# ProDoc_Schematic1_2026-04-23.net
KiCad netlist of a schematic drawn in EasyEDA Pro
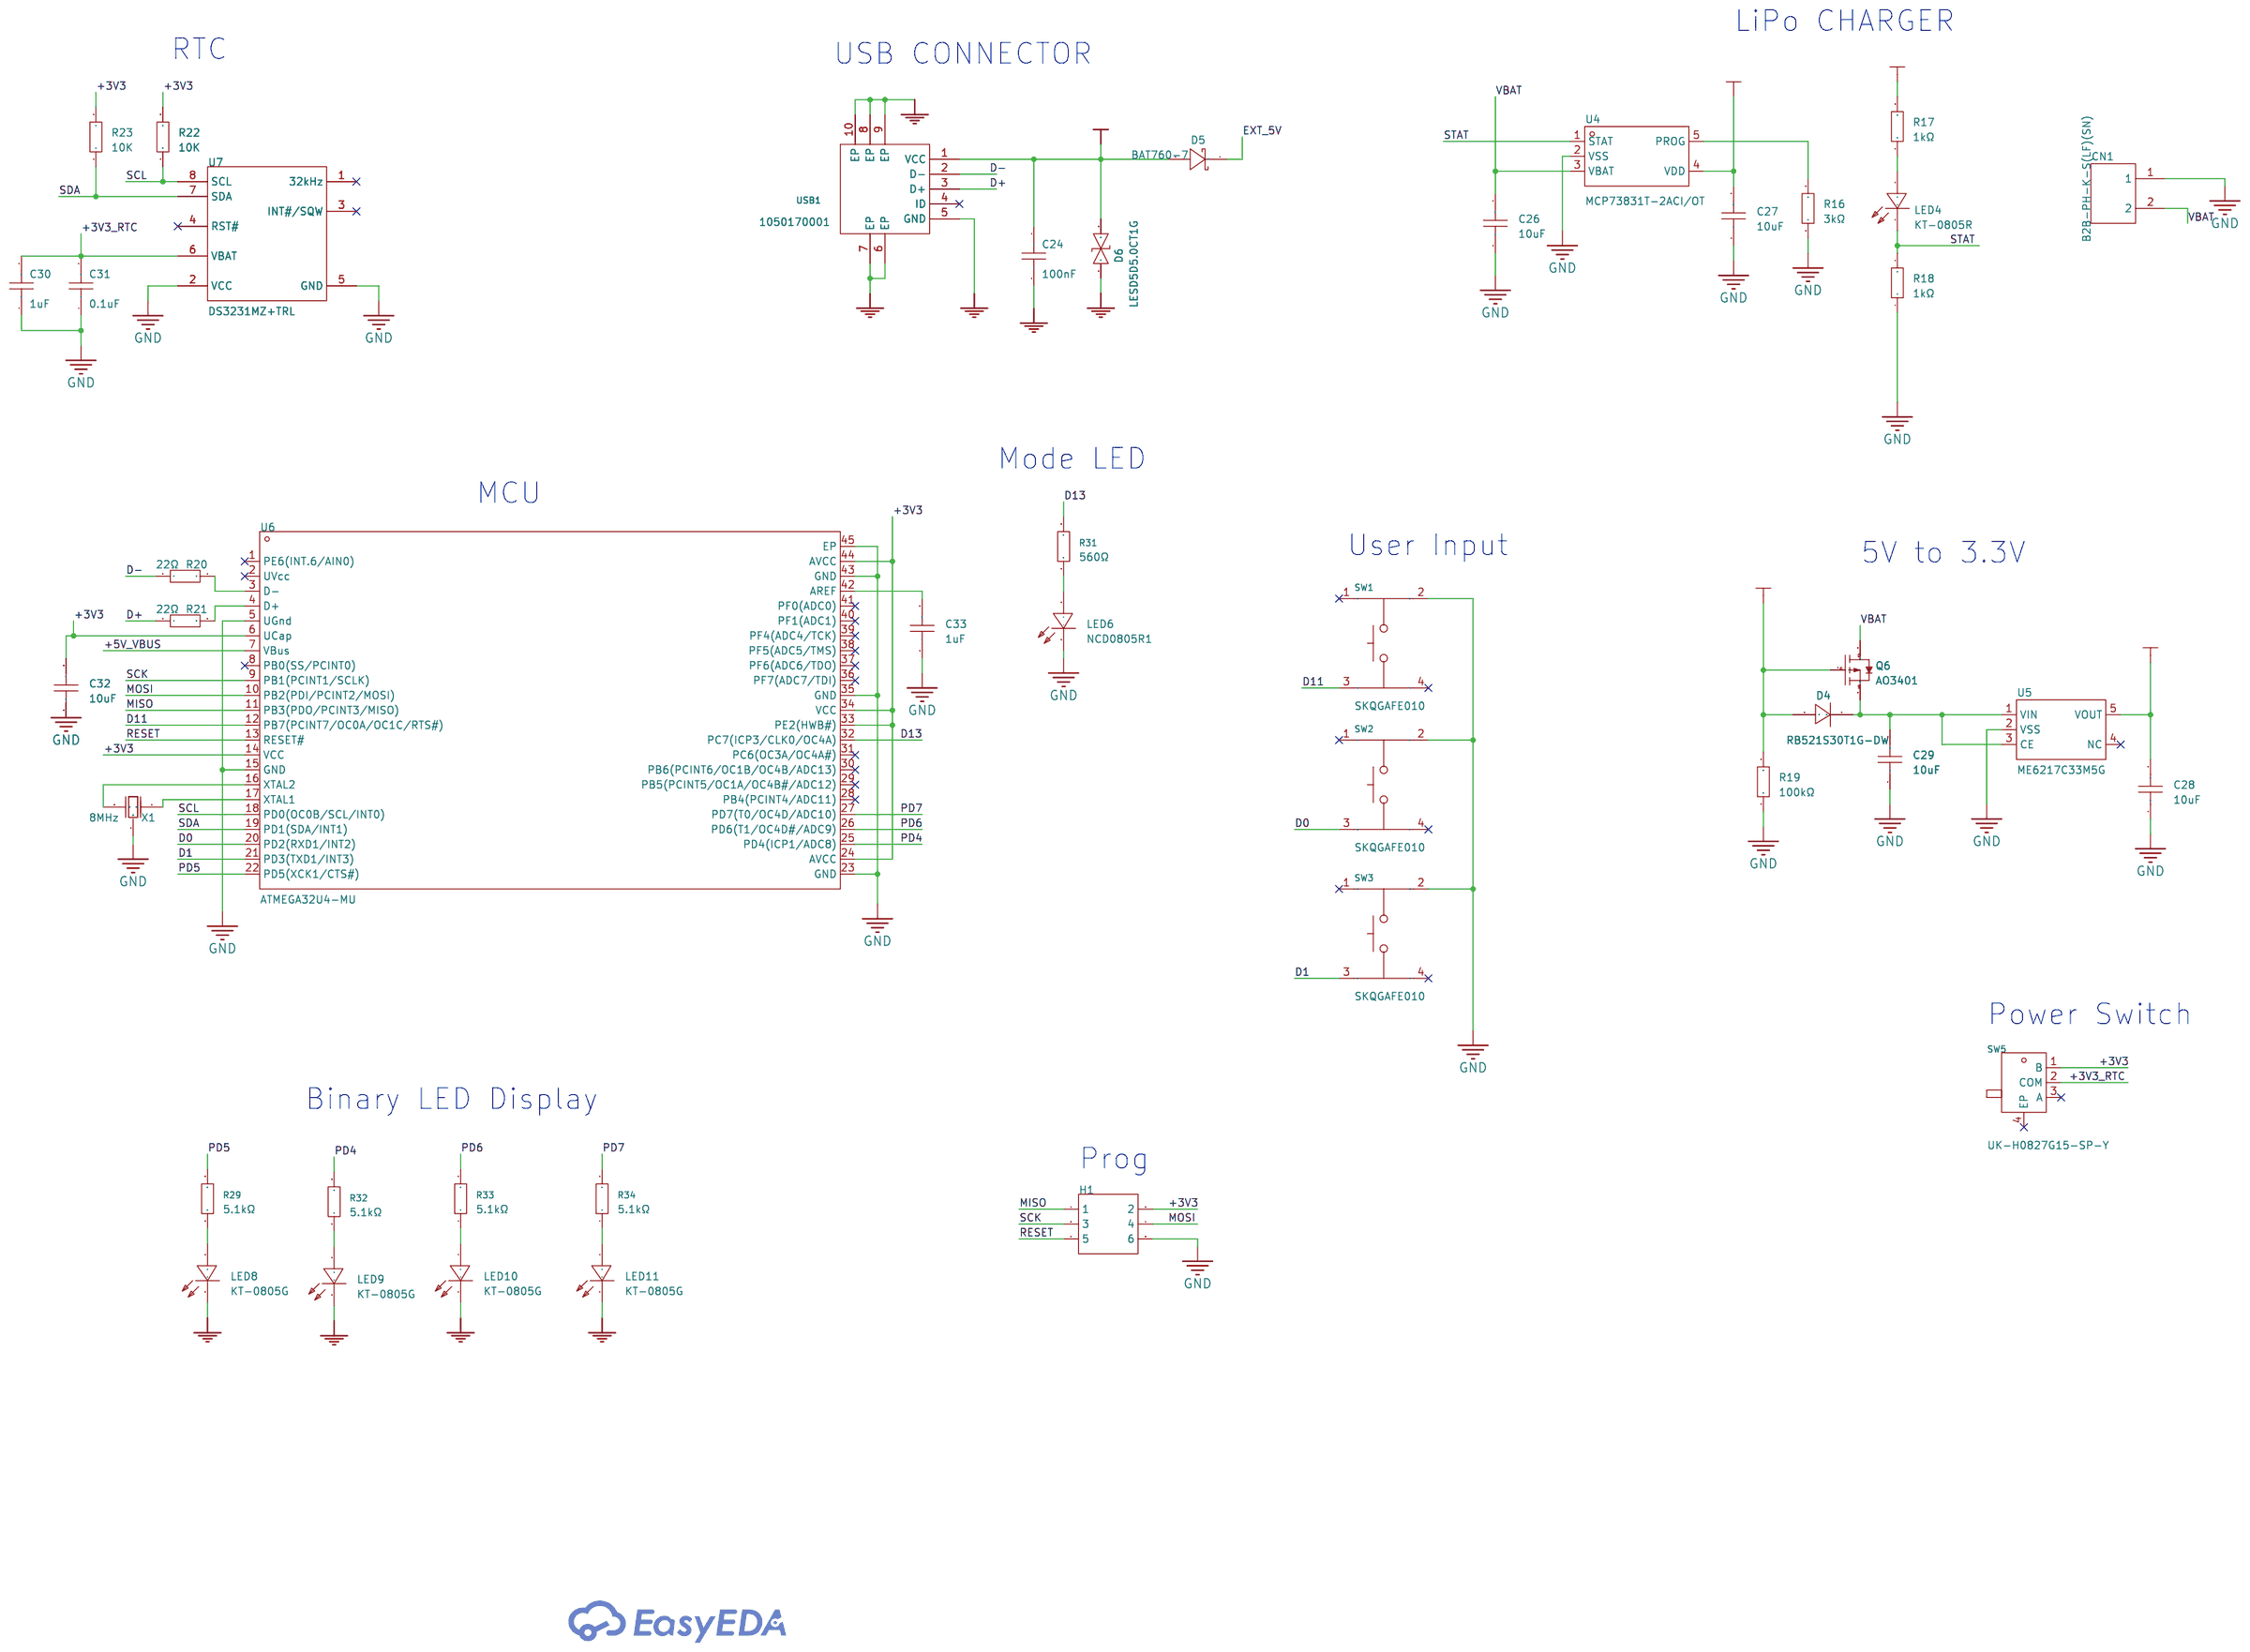
[diagram p0: schematic sheet]

(export (version "E")
  (design (tool "Eeschema 10.0.6"))
  (components
    (comp (ref "C24")
      (value "100nF")
      (footprint "easyedapro:C0402")
      (description "Capacitance:100nF Tolerance:±10% Tolerance:±10% Voltage Rating:16V Temperature Coefficient:X7R")
      (fields
        (field (name "Manufacturer Part") "CL05B104KO5NNNC")
        (field (name "Manufacturer") "SAMSUNG(三星)")
      )
      (libsource (lib "easyedapro") (part "CL05B104KO5NNNC"))
    )
    (comp (ref "C26")
      (value "10uF")
      (footprint "easyedapro:C0402")
      (description "Capacitance:10uF Tolerance:±20% Tolerance:±20% Voltage Rating:10V Temperature Coefficient:X5R")
      (fields
        (field (name "Manufacturer Part") "CL05A106MP5NUNC")
        (field (name "Manufacturer") "SAMSUNG(三星)")
      )
      (libsource (lib "easyedapro") (part "CL05A106MP5NUNC_C315248"))
    )
    (comp (ref "C27")
      (value "10uF")
      (footprint "easyedapro:C0402")
      (description "Capacitance:10uF Tolerance:±20% Tolerance:±20% Voltage Rating:10V Temperature Coefficient:X5R")
      (fields
        (field (name "Manufacturer Part") "CL05A106MP5NUNC")
        (field (name "Manufacturer") "SAMSUNG(三星)")
      )
      (libsource (lib "easyedapro") (part "CL05A106MP5NUNC_C315248"))
    )
    (comp (ref "C28")
      (value "10uF")
      (footprint "easyedapro:C0402")
      (description "Capacitance:10uF Tolerance:±20% Tolerance:±20% Voltage Rating:10V Temperature Coefficient:X5R")
      (fields
        (field (name "Manufacturer Part") "CL05A106MP5NUNC")
        (field (name "Manufacturer") "SAMSUNG(三星)")
      )
      (libsource (lib "easyedapro") (part "CL05A106MP5NUNC_C315248"))
    )
    (comp (ref "C29")
      (value "10uF")
      (footprint "easyedapro:C0402")
      (description "Capacitance:10uF Tolerance:±20% Tolerance:±20% Voltage Rating:10V Temperature Coefficient:X5R")
      (fields
        (field (name "Manufacturer Part") "CL05A106MP5NUNC")
        (field (name "Manufacturer") "SAMSUNG(三星)")
      )
      (libsource (lib "easyedapro") (part "CL05A106MP5NUNC_C315248"))
    )
    (comp (ref "C30")
      (value "1uF")
      (footprint "easyedapro:C0402")
      (description "Capacitance:100nF Tolerance:±10% Tolerance:±10% Voltage Rating:16V Temperature Coefficient:X7R")
      (fields
        (field (name "Manufacturer Part") "CL05B104KO5NNNC")
        (field (name "Manufacturer") "SAMSUNG(三星)")
      )
      (libsource (lib "easyedapro") (part "CL05B104KO5NNNC"))
    )
    (comp (ref "C31")
      (value "0.1uF")
      (footprint "easyedapro:C0402")
      (description "Capacitance:100nF Tolerance:±10% Tolerance:±10% Voltage Rating:16V Temperature Coefficient:X7R")
      (fields
        (field (name "Manufacturer Part") "CL05B104KO5NNNC")
        (field (name "Manufacturer") "SAMSUNG(三星)")
      )
      (libsource (lib "easyedapro") (part "CL05B104KO5NNNC"))
    )
    (comp (ref "C32")
      (value "10uF")
      (footprint "easyedapro:C0402")
      (description "Capacitance:10uF Tolerance:±20% Tolerance:±20% Voltage Rating:10V Temperature Coefficient:X5R")
      (fields
        (field (name "Manufacturer Part") "CL05A106MP5NUNC")
        (field (name "Manufacturer") "SAMSUNG(三星)")
      )
      (libsource (lib "easyedapro") (part "CL05A106MP5NUNC_C315248"))
    )
    (comp (ref "C33")
      (value "1uF")
      (footprint "easyedapro:C0402")
      (description "Capacitance:10uF Tolerance:±20% Tolerance:±20% Voltage Rating:10V Temperature Coefficient:X5R")
      (fields
        (field (name "Manufacturer Part") "CL05A106MP5NUNC")
        (field (name "Manufacturer") "SAMSUNG(三星)")
      )
      (libsource (lib "easyedapro") (part "CL05A106MP5NUNC_C315248"))
    )
    (comp (ref "CN1")
      (value "B2B-PH-K-S(LF)(SN)")
      (footprint "easyedapro:CONN-TH_B2B-PH-K-S")
      (fields (field (name "Manufacturer") "JST"))
      (libsource (lib "easyedapro") (part "B2B-PH-K-S(LF)(SN)"))
    )
    (comp (ref "D4")
      (value "RB521S30T1G-DW")
      (footprint "easyedapro:SOD-523_L1.2-W0.8-LS1.6-RD")
      (fields (field (name "Manufacturer") "DOWO(东沃)"))
      (libsource (lib "easyedapro") (part "RB521S30T1G_C27636108"))
    )
    (comp (ref "D5")
      (value "BAT760-7")
      (footprint "easyedapro:SOD-323_L1.7-W1.3-LS2.6-FD-1")
      (fields (field (name "Manufacturer") "DOWO(东沃)"))
      (libsource (lib "easyedapro") (part "BAT760-7_C27636120"))
    )
    (comp (ref "D6")
      (value "LESD5D5.0CT1G")
      (footprint "easyedapro:SOD-523_L1.2-W0.8-LS1.6-BI")
      (fields (field (name "Manufacturer") "LRC(乐山无线电)"))
      (libsource (lib "easyedapro") (part "LESD5D5.0CT1G"))
    )
    (comp (ref "H1")
      (value "~")
      (footprint "easyedapro:HDR-TH_6P-P2.54-V-F-R2-C3-S2.54")
      (libsource (lib "easyedapro") (part "HDR-F-2.54_2x3"))
    )
    (comp (ref "LED4")
      (value "KT-0805R")
      (footprint "easyedapro:LED0805-R-RD")
      (fields (field (name "Manufacturer") "KENTO"))
      (libsource (lib "easyedapro") (part "E6C0805UR"))
    )
    (comp (ref "LED6")
      (value "NCD0805R1")
      (fields (field (name "Manufacturer") "国星光电"))
      (libsource (lib "easyedapro") (part "FC-2012HRK-620D"))
    )
    (comp (ref "LED8")
      (value "KT-0805G")
      (footprint "easyedapro:LED0805-R-RD")
      (fields (field (name "Manufacturer") "KENTO"))
      (libsource (lib "easyedapro") (part "0805G (Green)"))
    )
    (comp (ref "LED9")
      (value "KT-0805G")
      (footprint "easyedapro:LED0805-R-RD")
      (fields (field (name "Manufacturer") "KENTO"))
      (libsource (lib "easyedapro") (part "0805G (Green)"))
    )
    (comp (ref "LED10")
      (value "KT-0805G")
      (footprint "easyedapro:LED0805-R-RD")
      (fields (field (name "Manufacturer") "KENTO"))
      (libsource (lib "easyedapro") (part "0805G (Green)"))
    )
    (comp (ref "LED11")
      (value "KT-0805G")
      (footprint "easyedapro:LED0805-R-RD")
      (fields (field (name "Manufacturer") "KENTO"))
      (libsource (lib "easyedapro") (part "0805G (Green)"))
    )
    (comp (ref "Q6")
      (value "AO3401")
      (footprint "easyedapro:SOT-23-3_L2.9-W1.3-P0.95-LS2.4-BR")
      (fields (field (name "Manufacturer") "KUU"))
      (libsource (lib "easyedapro") (part "AO3401_C2985640"))
    )
    (comp (ref "R16")
      (value "3kΩ")
      (footprint "easyedapro:R0603")
      (fields
        (field (name "Manufacturer Part") "0603WAF3001T5E")
        (field (name "Manufacturer") "UNI-ROYAL(厚声)")
      )
      (libsource (lib "easyedapro") (part "Res"))
    )
    (comp (ref "R17")
      (value "1kΩ")
      (footprint "easyedapro:R0603")
      (fields (field (name "Manufacturer Part") "RC0603FR-071KL") (field (name "Manufacturer") "YAGEO(国巨)"))
      (libsource (lib "easyedapro") (part "Res"))
    )
    (comp (ref "R18")
      (value "1kΩ")
      (footprint "easyedapro:R0603")
      (fields (field (name "Manufacturer Part") "RC0603FR-071KL") (field (name "Manufacturer") "YAGEO(国巨)"))
      (libsource (lib "easyedapro") (part "Res"))
    )
    (comp (ref "R19")
      (value "100kΩ")
      (footprint "easyedapro:R0603")
      (fields
        (field (name "Manufacturer Part") "0603WAF1003T5E")
        (field (name "Manufacturer") "UNI-ROYAL(厚声)")
      )
      (libsource (lib "easyedapro") (part "Res"))
    )
    (comp (ref "R20")
      (value "22Ω")
      (footprint "easyedapro:R0603")
      (fields
        (field (name "Manufacturer Part") "0603WAF1003T5E")
        (field (name "Manufacturer") "UNI-ROYAL(厚声)")
      )
      (libsource (lib "easyedapro") (part "Res"))
    )
    (comp (ref "R21")
      (value "22Ω")
      (footprint "easyedapro:R0603")
      (fields
        (field (name "Manufacturer Part") "0603WAF1003T5E")
        (field (name "Manufacturer") "UNI-ROYAL(厚声)")
      )
      (libsource (lib "easyedapro") (part "Res"))
    )
    (comp (ref "R22")
      (value "10K")
      (footprint "easyedapro:R0603")
      (libsource (lib "easyedapro") (part "Res"))
    )
    (comp (ref "R23")
      (value "10K")
      (footprint "easyedapro:R0603")
      (libsource (lib "easyedapro") (part "Res"))
    )
    (comp (ref "R29")
      (value "5.1kΩ")
      (footprint "easyedapro:R0402")
      (fields
        (field (name "Manufacturer Part") "0402WGF5101TCE")
        (field (name "Manufacturer") "UNI-ROYAL(厚声)")
      )
      (libsource (lib "easyedapro") (part "0402WGF5101TCE"))
    )
    (comp (ref "R31")
      (value "560Ω")
      (footprint "easyedapro:R0402")
      (fields
        (field (name "Manufacturer Part") "0402WGF5600TCE")
        (field (name "Manufacturer") "UNI-ROYAL(厚声)")
      )
      (libsource (lib "easyedapro") (part "0402WGF5600TCE"))
    )
    (comp (ref "R32")
      (value "5.1kΩ")
      (footprint "easyedapro:R0402")
      (fields
        (field (name "Manufacturer Part") "0402WGF5101TCE")
        (field (name "Manufacturer") "UNI-ROYAL(厚声)")
      )
      (libsource (lib "easyedapro") (part "0402WGF5101TCE"))
    )
    (comp (ref "R33")
      (value "5.1kΩ")
      (footprint "easyedapro:R0402")
      (fields
        (field (name "Manufacturer Part") "0402WGF5101TCE")
        (field (name "Manufacturer") "UNI-ROYAL(厚声)")
      )
      (libsource (lib "easyedapro") (part "0402WGF5101TCE"))
    )
    (comp (ref "R34")
      (value "5.1kΩ")
      (footprint "easyedapro:R0402")
      (fields
        (field (name "Manufacturer Part") "0402WGF5101TCE")
        (field (name "Manufacturer") "UNI-ROYAL(厚声)")
      )
      (libsource (lib "easyedapro") (part "0402WGF5101TCE"))
    )
    (comp (ref "SW1")
      (value "SKQGAFE010")
      (footprint "easyedapro:SW-SMD_4P-L5.2-W5.2-P3.70-LS6.4")
      (fields (field (name "Manufacturer") "ALPSALPINE(阿尔卑斯阿尔派)"))
      (libsource (lib "easyedapro") (part "SKQGAFE010"))
    )
    (comp (ref "SW2")
      (value "SKQGAFE010")
      (footprint "easyedapro:SW-SMD_4P-L5.2-W5.2-P3.70-LS6.4")
      (fields (field (name "Manufacturer") "ALPSALPINE(阿尔卑斯阿尔派)"))
      (libsource (lib "easyedapro") (part "SKQGAFE010"))
    )
    (comp (ref "SW3")
      (value "SKQGAFE010")
      (footprint "easyedapro:SW-SMD_4P-L5.2-W5.2-P3.70-LS6.4")
      (fields (field (name "Manufacturer") "ALPSALPINE(阿尔卑斯阿尔派)"))
      (libsource (lib "easyedapro") (part "SKQGAFE010"))
    )
    (comp (ref "SW5")
      (value "UK-H0827G15-SP-Y")
      (footprint "easyedapro:SW-SMD_UK-H0827G15-SP-Y")
      (description "Current Rating:50mA Voltage Rating:12V Life:10,000 Cycles")
      (fields (field (name "Manufacturer") "USAKRO(美韩)"))
      (libsource (lib "easyedapro") (part "UK-H0827G15-SP-Y"))
    )
    (comp (ref "U4")
      (value "MCP73831T-2ACI/OT")
      (footprint "easyedapro:SOT-23-5_L3.0-W1.7-P0.95-LS2.8-BL")
      (fields (field (name "Manufacturer") "MICROCHIP(美国微芯)"))
      (libsource (lib "easyedapro") (part "MCP73831T-2ACI/OT"))
    )
    (comp (ref "U5")
      (value "ME6217C33M5G")
      (footprint "easyedapro:SOT-23-5_L3.0-W1.7-P0.95-LS2.8-BR")
      (fields (field (name "Manufacturer") "MICRONE(南京微盟)"))
      (libsource (lib "easyedapro") (part "ME6217C33M5G"))
    )
    (comp (ref "U6")
      (value "ATMEGA32U4-MU")
      (footprint "easyedapro:VQFN-44_L7.0-W7.0-P0.50-BL-EP5.2")
      (fields (field (name "Manufacturer") "MICROCHIP(美国微芯)"))
      (libsource (lib "easyedapro") (part "ATMEGA32U4-MU"))
    )
    (comp (ref "U7")
      (value "DS3231MZ+TRL")
      (footprint "easyedapro:SOIC-8_L4.9-W3.9-P1.27-LS6.0-BL")
      (fields (field (name "Manufacturer") "ADI(亚德诺)/MAXIM(美信)"))
      (libsource (lib "easyedapro") (part "DS3231MZ+"))
    )
    (comp (ref "USB1")
      (value "1050170001")
      (footprint "easyedapro:MICRO-USB-SMD_105017-0001")
      (fields (field (name "Manufacturer") "MOLEX"))
      (libsource (lib "easyedapro") (part "105017-0001"))
    )
    (comp (ref "X1")
      (value "8MHz")
      (footprint "easyedapro:OSC-SMD_3P-L3.2-W1.3-P1.20-L")
      (fields
        (field (name "Manufacturer Part") "CSTNE8M00GH5C000R0")
        (field (name "Manufacturer") "muRata(村田)")
      )
      (libsource (lib "easyedapro") (part "CSTNE8M00GH5C000R0"))
    )
  )
  (nets
    (net (code "1") (name "+3V3_RTC") (class "Default")
      (node (ref "C28") (pin "2") (pinfunction "2_2") (pintype "unspecified"))
      (node (ref "C30") (pin "2") (pinfunction "2_2") (pintype "unspecified"))
      (node (ref "C31") (pin "2") (pinfunction "2_2") (pintype "unspecified"))
      (node (ref "SW5") (pin "2") (pinfunction "COM_2") (pintype "input"))
      (node (ref "U5") (pin "5") (pinfunction "VOUT_5") (pintype "unspecified"))
      (node (ref "U7") (pin "6") (pinfunction "VBAT_6") (pintype "unspecified"))
    )
    (net (code "2") (name "+5V_VBUS") (class "Default")
      (node (ref "C24") (pin "2") (pinfunction "2_2") (pintype "unspecified"))
      (node (ref "D5") (pin "2") (pinfunction "A_2") (pintype "unspecified"))
      (node (ref "D6") (pin "2") (pinfunction "2_2") (pintype "unspecified"))
      (node (ref "U6") (pin "7") (pinfunction "VBus_7") (pintype "unspecified"))
      (node (ref "USB1") (pin "1") (pinfunction "VCC_1") (pintype "input"))
    )
    (net (code "3") (name "/+3V3") (class "Default")
      (node (ref "C32") (pin "2") (pinfunction "2_2") (pintype "unspecified"))
      (node (ref "H1") (pin "2") (pinfunction "2_2") (pintype "input"))
      (node (ref "R22") (pin "2") (pinfunction "2_2") (pintype "input"))
      (node (ref "R23") (pin "2") (pinfunction "2_2") (pintype "input"))
      (node (ref "SW5") (pin "1") (pinfunction "B_1") (pintype "input"))
      (node (ref "U6") (pin "14") (pinfunction "VCC_14") (pintype "unspecified"))
      (node (ref "U6") (pin "24") (pinfunction "AVCC_24") (pintype "unspecified"))
      (node (ref "U6") (pin "33") (pinfunction "PE2(HWB#)_33") (pintype "unspecified"))
      (node (ref "U6") (pin "34") (pinfunction "VCC_34") (pintype "unspecified"))
      (node (ref "U6") (pin "44") (pinfunction "AVCC_44") (pintype "unspecified"))
      (node (ref "U6") (pin "6") (pinfunction "UCap_6") (pintype "unspecified"))
    )
    (net (code "4") (name "/D+") (class "Default")
      (node (ref "R21") (pin "1") (pinfunction "1_1") (pintype "input"))
      (node (ref "USB1") (pin "3") (pinfunction "D+_3") (pintype "input"))
    )
    (net (code "5") (name "/D-") (class "Default")
      (node (ref "R20") (pin "2") (pinfunction "2_2") (pintype "input"))
      (node (ref "USB1") (pin "2") (pinfunction "D-_2") (pintype "input"))
    )
    (net (code "6") (name "/D0") (class "Default")
      (node (ref "SW2") (pin "3") (pinfunction "3_3") (pintype "input"))
      (node (ref "U6") (pin "20") (pinfunction "PD2(RXD1/INT2)_20") (pintype "unspecified"))
    )
    (net (code "7") (name "/D1") (class "Default")
      (node (ref "SW3") (pin "3") (pinfunction "3_3") (pintype "input"))
      (node (ref "U6") (pin "21") (pinfunction "PD3(TXD1/INT3)_21") (pintype "unspecified"))
    )
    (net (code "8") (name "/D11") (class "Default")
      (node (ref "SW1") (pin "3") (pinfunction "3_3") (pintype "input"))
      (node (ref "U6") (pin "12") (pinfunction "PB7(PCINT7/OC0A/OC1C/RTS#)_12") (pintype "unspecified"))
    )
    (net (code "9") (name "/D13") (class "Default")
      (node (ref "R31") (pin "2") (pinfunction "2_2") (pintype "input"))
      (node (ref "U6") (pin "32") (pinfunction "PC7(ICP3/CLK0/OC4A)_32") (pintype "unspecified"))
    )
    (net (code "10") (name "/MISO") (class "Default")
      (node (ref "H1") (pin "1") (pinfunction "1_1") (pintype "input"))
      (node (ref "U6") (pin "11") (pinfunction "PB3(PDO/PCINT3/MISO)_11") (pintype "unspecified"))
    )
    (net (code "11") (name "/MOSI") (class "Default")
      (node (ref "H1") (pin "4") (pinfunction "4_4") (pintype "input"))
      (node (ref "U6") (pin "10") (pinfunction "PB2(PDI/PCINT2/MOSI)_10") (pintype "unspecified"))
    )
    (net (code "12") (name "/PD4") (class "Default")
      (node (ref "R32") (pin "2") (pinfunction "2_2") (pintype "input"))
      (node (ref "U6") (pin "25") (pinfunction "PD4(ICP1/ADC8)_25") (pintype "unspecified"))
    )
    (net (code "13") (name "/PD5") (class "Default")
      (node (ref "R29") (pin "2") (pinfunction "2_2") (pintype "input"))
      (node (ref "U6") (pin "22") (pinfunction "PD5(XCK1/CTS#)_22") (pintype "unspecified"))
    )
    (net (code "14") (name "/PD6") (class "Default")
      (node (ref "R33") (pin "2") (pinfunction "2_2") (pintype "input"))
      (node (ref "U6") (pin "26") (pinfunction "PD6(T1/OC4D#/ADC9)_26") (pintype "unspecified"))
    )
    (net (code "15") (name "/PD7") (class "Default")
      (node (ref "R34") (pin "2") (pinfunction "2_2") (pintype "input"))
      (node (ref "U6") (pin "27") (pinfunction "PD7(T0/OC4D/ADC10)_27") (pintype "unspecified"))
    )
    (net (code "16") (name "/RESET") (class "Default")
      (node (ref "H1") (pin "5") (pinfunction "5_5") (pintype "input"))
      (node (ref "U6") (pin "13") (pinfunction "RESET#_13") (pintype "unspecified"))
    )
    (net (code "17") (name "/SCK") (class "Default")
      (node (ref "H1") (pin "3") (pinfunction "3_3") (pintype "input"))
      (node (ref "U6") (pin "9") (pinfunction "PB1(PCINT1/SCLK)_9") (pintype "unspecified"))
    )
    (net (code "18") (name "/SCL") (class "Default")
      (node (ref "R22") (pin "1") (pinfunction "1_1") (pintype "input"))
      (node (ref "U6") (pin "18") (pinfunction "PD0(OC0B/SCL/INT0)_18") (pintype "unspecified"))
      (node (ref "U7") (pin "8") (pinfunction "SCL_8") (pintype "unspecified"))
    )
    (net (code "19") (name "/SDA") (class "Default")
      (node (ref "R23") (pin "1") (pinfunction "1_1") (pintype "input"))
      (node (ref "U6") (pin "19") (pinfunction "PD1(SDA/INT1)_19") (pintype "unspecified"))
      (node (ref "U7") (pin "7") (pinfunction "SDA_7") (pintype "bidirectional"))
    )
    (net (code "20") (name "/STAT") (class "Default")
      (node (ref "LED4") (pin "2") (pinfunction "K_2") (pintype "unspecified"))
      (node (ref "R18") (pin "2") (pinfunction "2_2") (pintype "input"))
      (node (ref "U4") (pin "1") (pinfunction "STAT_1") (pintype "unspecified"))
    )
    (net (code "21") (name "/VBAT") (class "Default")
      (node (ref "C26") (pin "2") (pinfunction "2_2") (pintype "unspecified"))
      (node (ref "CN1") (pin "2") (pinfunction "2_2") (pintype "input"))
      (node (ref "Q6") (pin "3") (pinfunction "D_3") (pintype "unspecified"))
      (node (ref "U4") (pin "3") (pinfunction "VBAT_3") (pintype "unspecified"))
    )
    (net (code "22") (name "EXT_5V") (class "Default")
      (node (ref "C27") (pin "2") (pinfunction "2_2") (pintype "unspecified"))
      (node (ref "D4") (pin "2") (pinfunction "A_2") (pintype "unspecified"))
      (node (ref "D5") (pin "1") (pinfunction "C_1") (pintype "unspecified"))
      (node (ref "Q6") (pin "1") (pinfunction "G_1") (pintype "unspecified"))
      (node (ref "R17") (pin "2") (pinfunction "2_2") (pintype "input"))
      (node (ref "R19") (pin "2") (pinfunction "2_2") (pintype "input"))
      (node (ref "U4") (pin "4") (pinfunction "VDD_4") (pintype "unspecified"))
    )
    (net (code "23") (name "GND") (class "Default")
      (node (ref "C24") (pin "1") (pinfunction "1_1") (pintype "unspecified"))
      (node (ref "C26") (pin "1") (pinfunction "1_1") (pintype "unspecified"))
      (node (ref "C27") (pin "1") (pinfunction "1_1") (pintype "unspecified"))
      (node (ref "C28") (pin "1") (pinfunction "1_1") (pintype "unspecified"))
      (node (ref "C29") (pin "1") (pinfunction "1_1") (pintype "unspecified"))
      (node (ref "C30") (pin "1") (pinfunction "1_1") (pintype "unspecified"))
      (node (ref "C31") (pin "1") (pinfunction "1_1") (pintype "unspecified"))
      (node (ref "C32") (pin "1") (pinfunction "1_1") (pintype "unspecified"))
      (node (ref "C33") (pin "1") (pinfunction "1_1") (pintype "unspecified"))
      (node (ref "CN1") (pin "1") (pinfunction "1_1") (pintype "input"))
      (node (ref "D6") (pin "1") (pinfunction "1_1") (pintype "unspecified"))
      (node (ref "H1") (pin "6") (pinfunction "6_6") (pintype "input"))
      (node (ref "LED10") (pin "2") (pinfunction "K_2") (pintype "unspecified"))
      (node (ref "LED11") (pin "2") (pinfunction "K_2") (pintype "unspecified"))
      (node (ref "LED6") (pin "2") (pinfunction "-_2") (pintype "unspecified"))
      (node (ref "LED8") (pin "2") (pinfunction "K_2") (pintype "unspecified"))
      (node (ref "LED9") (pin "2") (pinfunction "K_2") (pintype "unspecified"))
      (node (ref "R16") (pin "1") (pinfunction "1_1") (pintype "input"))
      (node (ref "R18") (pin "1") (pinfunction "1_1") (pintype "input"))
      (node (ref "R19") (pin "1") (pinfunction "1_1") (pintype "input"))
      (node (ref "SW1") (pin "2") (pinfunction "2_2") (pintype "input"))
      (node (ref "SW2") (pin "2") (pinfunction "2_2") (pintype "input"))
      (node (ref "SW3") (pin "2") (pinfunction "2_2") (pintype "input"))
      (node (ref "U4") (pin "2") (pinfunction "VSS_2") (pintype "unspecified"))
      (node (ref "U5") (pin "2") (pinfunction "VSS_2") (pintype "unspecified"))
      (node (ref "U6") (pin "15") (pinfunction "GND_15") (pintype "unspecified"))
      (node (ref "U6") (pin "23") (pinfunction "GND_23") (pintype "unspecified"))
      (node (ref "U6") (pin "35") (pinfunction "GND_35") (pintype "unspecified"))
      (node (ref "U6") (pin "43") (pinfunction "GND_43") (pintype "unspecified"))
      (node (ref "U6") (pin "45") (pinfunction "EP_45") (pintype "unspecified"))
      (node (ref "U6") (pin "5") (pinfunction "UGnd_5") (pintype "unspecified"))
      (node (ref "U7") (pin "2") (pinfunction "VCC_2") (pintype "unspecified"))
      (node (ref "U7") (pin "5") (pinfunction "GND_5") (pintype "unspecified"))
      (node (ref "USB1") (pin "10") (pinfunction "EP_10") (pintype "input"))
      (node (ref "USB1") (pin "5") (pinfunction "GND_5") (pintype "input"))
      (node (ref "USB1") (pin "6") (pinfunction "EP_6") (pintype "input"))
      (node (ref "USB1") (pin "7") (pinfunction "EP_7") (pintype "input"))
      (node (ref "USB1") (pin "8") (pinfunction "EP_8") (pintype "input"))
      (node (ref "USB1") (pin "9") (pinfunction "EP_9") (pintype "input"))
      (node (ref "X1") (pin "2") (pinfunction "GND_2") (pintype "input"))
    )
    (net (code "24") (name "Net-(D4-C)") (class "Default")
      (node (ref "C29") (pin "2") (pinfunction "2_2") (pintype "unspecified"))
      (node (ref "D4") (pin "1") (pinfunction "C_1") (pintype "unspecified"))
      (node (ref "Q6") (pin "2") (pinfunction "S_2") (pintype "unspecified"))
      (node (ref "U5") (pin "1") (pinfunction "VIN_1") (pintype "unspecified"))
      (node (ref "U5") (pin "3") (pinfunction "CE_3") (pintype "unspecified"))
    )
    (net (code "25") (name "Net-(LED4-A)") (class "Default")
      (node (ref "LED4") (pin "1") (pinfunction "A_1") (pintype "unspecified"))
      (node (ref "R17") (pin "1") (pinfunction "1_1") (pintype "input"))
    )
    (net (code "26") (name "Net-(LED6-+)") (class "Default")
      (node (ref "LED6") (pin "1") (pinfunction "+_1") (pintype "unspecified"))
      (node (ref "R31") (pin "1") (pinfunction "1_1") (pintype "input"))
    )
    (net (code "27") (name "Net-(LED8-A)") (class "Default")
      (node (ref "LED8") (pin "1") (pinfunction "A_1") (pintype "unspecified"))
      (node (ref "R29") (pin "1") (pinfunction "1_1") (pintype "input"))
    )
    (net (code "28") (name "Net-(LED9-A)") (class "Default")
      (node (ref "LED9") (pin "1") (pinfunction "A_1") (pintype "unspecified"))
      (node (ref "R32") (pin "1") (pinfunction "1_1") (pintype "input"))
    )
    (net (code "29") (name "Net-(LED10-A)") (class "Default")
      (node (ref "LED10") (pin "1") (pinfunction "A_1") (pintype "unspecified"))
      (node (ref "R33") (pin "1") (pinfunction "1_1") (pintype "input"))
    )
    (net (code "30") (name "Net-(LED11-A)") (class "Default")
      (node (ref "LED11") (pin "1") (pinfunction "A_1") (pintype "unspecified"))
      (node (ref "R34") (pin "1") (pinfunction "1_1") (pintype "input"))
    )
    (net (code "31") (name "Net-(U4-PROG)") (class "Default")
      (node (ref "R16") (pin "2") (pinfunction "2_2") (pintype "input"))
      (node (ref "U4") (pin "5") (pinfunction "PROG_5") (pintype "unspecified"))
    )
    (net (code "32") (name "Net-(U6-AREF)") (class "Default")
      (node (ref "C33") (pin "2") (pinfunction "2_2") (pintype "unspecified"))
      (node (ref "U6") (pin "42") (pinfunction "AREF_42") (pintype "unspecified"))
    )
    (net (code "33") (name "Net-(U6-D+)") (class "Default")
      (node (ref "R21") (pin "2") (pinfunction "2_2") (pintype "input"))
      (node (ref "U6") (pin "4") (pinfunction "D+_4") (pintype "unspecified"))
    )
    (net (code "34") (name "Net-(U6-D-)") (class "Default")
      (node (ref "R20") (pin "1") (pinfunction "1_1") (pintype "input"))
      (node (ref "U6") (pin "3") (pinfunction "D-_3") (pintype "unspecified"))
    )
    (net (code "35") (name "Net-(U6-XTAL1)") (class "Default")
      (node (ref "U6") (pin "17") (pinfunction "XTAL1_17") (pintype "unspecified"))
      (node (ref "X1") (pin "1") (pinfunction "OSC1_1") (pintype "input"))
    )
    (net (code "36") (name "Net-(U6-XTAL2)") (class "Default")
      (node (ref "U6") (pin "16") (pinfunction "XTAL2_16") (pintype "unspecified"))
      (node (ref "X1") (pin "3") (pinfunction "OSC2_3") (pintype "input"))
    )
    (net (code "37") (name "unconnected-(SW1-Pad1)") (class "Default")
      (node (ref "SW1") (pin "1") (pinfunction "1_1") (pintype "input+no_connect"))
    )
    (net (code "38") (name "unconnected-(SW1-Pad4)") (class "Default")
      (node (ref "SW1") (pin "4") (pinfunction "4_4") (pintype "input+no_connect"))
    )
    (net (code "39") (name "unconnected-(SW2-Pad1)") (class "Default")
      (node (ref "SW2") (pin "1") (pinfunction "1_1") (pintype "input+no_connect"))
    )
    (net (code "40") (name "unconnected-(SW2-Pad4)") (class "Default")
      (node (ref "SW2") (pin "4") (pinfunction "4_4") (pintype "input+no_connect"))
    )
    (net (code "41") (name "unconnected-(SW3-Pad1)") (class "Default")
      (node (ref "SW3") (pin "1") (pinfunction "1_1") (pintype "input+no_connect"))
    )
    (net (code "42") (name "unconnected-(SW3-Pad4)") (class "Default")
      (node (ref "SW3") (pin "4") (pinfunction "4_4") (pintype "input+no_connect"))
    )
    (net (code "43") (name "unconnected-(SW5-A-Pad3)") (class "Default")
      (node (ref "SW5") (pin "3") (pinfunction "A_3") (pintype "input+no_connect"))
    )
    (net (code "44") (name "unconnected-(SW5-EP-Pad4)") (class "Default")
      (node (ref "SW5") (pin "4") (pinfunction "EP_4") (pintype "input+no_connect"))
    )
    (net (code "45") (name "unconnected-(U5-NC-Pad4)") (class "Default")
      (node (ref "U5") (pin "4") (pinfunction "NC_4") (pintype "unspecified+no_connect"))
    )
    (net (code "46") (name "unconnected-(U6-PB0(SS{slash}PCINT0)-Pad8)") (class "Default")
      (node (ref "U6") (pin "8") (pinfunction "PB0(SS/PCINT0)_8") (pintype "unspecified+no_connect"))
    )
    (net (code "47") (name "unconnected-(U6-PB4(PCINT4{slash}ADC11)-Pad28)") (class "Default")
      (node (ref "U6") (pin "28") (pinfunction "PB4(PCINT4/ADC11)_28") (pintype "unspecified+no_connect"))
    )
    (net (code "48") (name "unconnected-(U6-PB5(PCINT5{slash}OC1A{slash}OC4B#{slash}ADC12)-Pad29)") (class "Default")
      (node (ref "U6") (pin "29") (pinfunction "PB5(PCINT5/OC1A/OC4B#/ADC12)_29") (pintype "unspecified+no_connect"))
    )
    (net (code "49") (name "unconnected-(U6-PB6(PCINT6{slash}OC1B{slash}OC4B{slash}ADC13)-Pad30)") (class "Default")
      (node (ref "U6") (pin "30") (pinfunction "PB6(PCINT6/OC1B/OC4B/ADC13)_30") (pintype "unspecified+no_connect"))
    )
    (net (code "50") (name "unconnected-(U6-PC6(OC3A{slash}OC4A#)-Pad31)") (class "Default")
      (node (ref "U6") (pin "31") (pinfunction "PC6(OC3A/OC4A#)_31") (pintype "unspecified+no_connect"))
    )
    (net (code "51") (name "unconnected-(U6-PE6(INT.6{slash}AIN0)-Pad1)") (class "Default")
      (node (ref "U6") (pin "1") (pinfunction "PE6(INT.6/AIN0)_1") (pintype "unspecified+no_connect"))
    )
    (net (code "52") (name "unconnected-(U6-PF0(ADC0)-Pad41)") (class "Default")
      (node (ref "U6") (pin "41") (pinfunction "PF0(ADC0)_41") (pintype "unspecified+no_connect"))
    )
    (net (code "53") (name "unconnected-(U6-PF1(ADC1)-Pad40)") (class "Default")
      (node (ref "U6") (pin "40") (pinfunction "PF1(ADC1)_40") (pintype "unspecified+no_connect"))
    )
    (net (code "54") (name "unconnected-(U6-PF4(ADC4{slash}TCK)-Pad39)") (class "Default")
      (node (ref "U6") (pin "39") (pinfunction "PF4(ADC4/TCK)_39") (pintype "unspecified+no_connect"))
    )
    (net (code "55") (name "unconnected-(U6-PF5(ADC5{slash}TMS)-Pad38)") (class "Default")
      (node (ref "U6") (pin "38") (pinfunction "PF5(ADC5/TMS)_38") (pintype "unspecified+no_connect"))
    )
    (net (code "56") (name "unconnected-(U6-PF6(ADC6{slash}TDO)-Pad37)") (class "Default")
      (node (ref "U6") (pin "37") (pinfunction "PF6(ADC6/TDO)_37") (pintype "unspecified+no_connect"))
    )
    (net (code "57") (name "unconnected-(U6-PF7(ADC7{slash}TDI)-Pad36)") (class "Default")
      (node (ref "U6") (pin "36") (pinfunction "PF7(ADC7/TDI)_36") (pintype "unspecified+no_connect"))
    )
    (net (code "58") (name "unconnected-(U6-UVcc-Pad2)") (class "Default")
      (node (ref "U6") (pin "2") (pinfunction "UVcc_2") (pintype "unspecified+no_connect"))
    )
    (net (code "59") (name "unconnected-(U7-32kHz-Pad1)") (class "Default")
      (node (ref "U7") (pin "1") (pinfunction "32kHz_1") (pintype "unspecified+no_connect"))
    )
    (net (code "60") (name "unconnected-(U7-INT#{slash}SQW-Pad3)") (class "Default")
      (node (ref "U7") (pin "3") (pinfunction "INT#/SQW_3") (pintype "bidirectional+no_connect"))
    )
    (net (code "61") (name "unconnected-(U7-RST#-Pad4)") (class "Default")
      (node (ref "U7") (pin "4") (pinfunction "RST#_4") (pintype "bidirectional+no_connect"))
    )
    (net (code "62") (name "unconnected-(USB1-ID-Pad4)") (class "Default")
      (node (ref "USB1") (pin "4") (pinfunction "ID_4") (pintype "input+no_connect"))
    )
  )
)
